# TI_ADC_VOLTAGE.net
KiCad netlist of a schematic drawn in Altium Designer
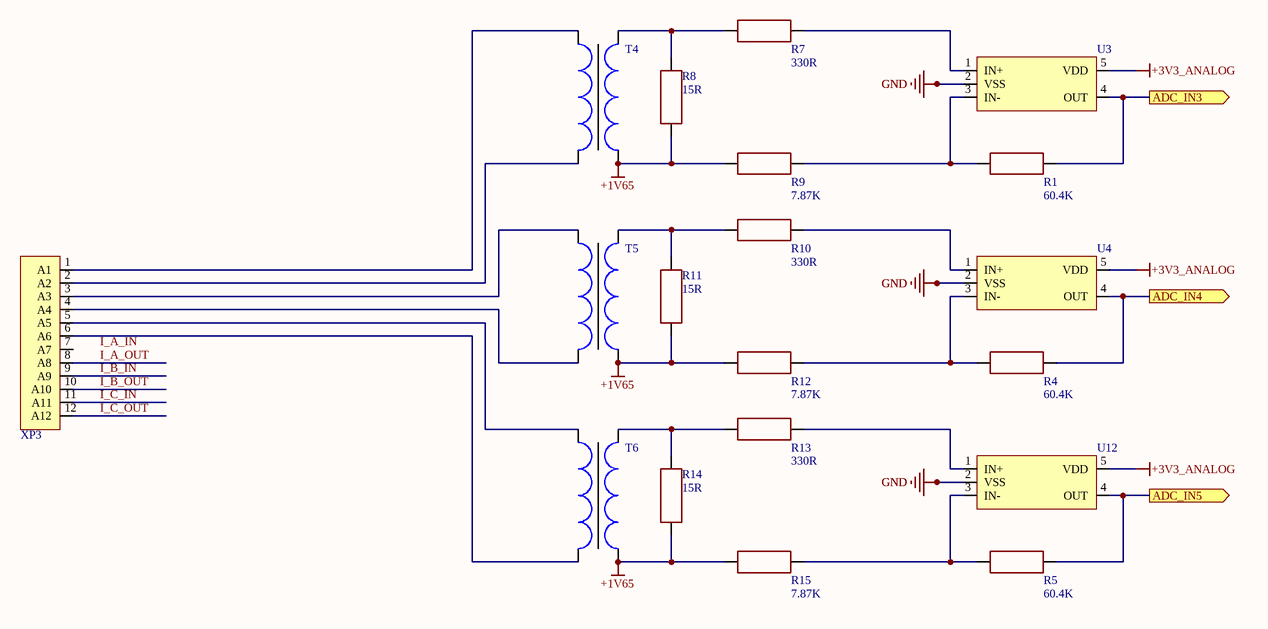
[diagram p0: TI_ADC_VOLTAGE.SchDoc]

(export (version "E")
  (design (tool "Eeschema 10.0.6"))
  (components
    (comp (ref "R1")
      (value "60.4K")
      (footprint "RES: 0603")
      (fields
        (field (name "POWER") "0.1W")
        (field (name "TOLERANCE") "±5%")
        (field (name "Comment") "Resistor_0603")
      )
      (libsource (lib "") (part "Resistor_0603_1"))
    )
    (comp (ref "R4")
      (value "60.4K")
      (footprint "RES: 0603")
      (fields
        (field (name "POWER") "0.1W")
        (field (name "TOLERANCE") "±5%")
        (field (name "Comment") "Resistor_0603")
      )
      (libsource (lib "") (part "Resistor_0603_1"))
    )
    (comp (ref "R5")
      (value "60.4K")
      (footprint "RES: 0603")
      (fields
        (field (name "POWER") "0.1W")
        (field (name "TOLERANCE") "±5%")
        (field (name "Comment") "Resistor_0603")
      )
      (libsource (lib "") (part "Resistor_0603_1"))
    )
    (comp (ref "R7")
      (value "330R")
      (footprint "RES: 0603")
      (fields
        (field (name "POWER") "0.1W")
        (field (name "TOLERANCE") "±5%")
        (field (name "Comment") "Resistor_0603")
      )
      (libsource (lib "resistor") (part "Resistor_0603"))
    )
    (comp (ref "R8")
      (value "15R")
      (footprint "RES: 0603")
      (fields
        (field (name "POWER") "0.1W")
        (field (name "TOLERANCE") "±5%")
        (field (name "Comment") "Resistor_0603")
      )
      (libsource (lib "") (part "Resistor_0603_1"))
    )
    (comp (ref "R9")
      (value "7.87K")
      (footprint "RES: 0603")
      (fields
        (field (name "POWER") "0.1W")
        (field (name "TOLERANCE") "±5%")
        (field (name "Comment") "Resistor_0603")
      )
      (libsource (lib "resistor") (part "Resistor_0603"))
    )
    (comp (ref "R10")
      (value "330R")
      (footprint "RES: 0603")
      (fields
        (field (name "POWER") "0.1W")
        (field (name "TOLERANCE") "±5%")
        (field (name "Comment") "Resistor_0603")
      )
      (libsource (lib "resistor") (part "Resistor_0603"))
    )
    (comp (ref "R11")
      (value "15R")
      (footprint "RES: 0603")
      (fields
        (field (name "POWER") "0.1W")
        (field (name "TOLERANCE") "±5%")
        (field (name "Comment") "Resistor_0603")
      )
      (libsource (lib "") (part "Resistor_0603_1"))
    )
    (comp (ref "R12")
      (value "7.87K")
      (footprint "RES: 0603")
      (fields
        (field (name "POWER") "0.1W")
        (field (name "TOLERANCE") "±5%")
        (field (name "Comment") "Resistor_0603")
      )
      (libsource (lib "resistor") (part "Resistor_0603"))
    )
    (comp (ref "R13")
      (value "330R")
      (footprint "RES: 0603")
      (fields
        (field (name "POWER") "0.1W")
        (field (name "TOLERANCE") "±5%")
        (field (name "Comment") "Resistor_0603")
      )
      (libsource (lib "resistor") (part "Resistor_0603"))
    )
    (comp (ref "R14")
      (value "15R")
      (footprint "RES: 0603")
      (fields
        (field (name "POWER") "0.1W")
        (field (name "TOLERANCE") "±5%")
        (field (name "Comment") "Resistor_0603")
      )
      (libsource (lib "") (part "Resistor_0603_1"))
    )
    (comp (ref "R15")
      (value "7.87K")
      (footprint "RES: 0603")
      (fields
        (field (name "POWER") "0.1W")
        (field (name "TOLERANCE") "±5%")
        (field (name "Comment") "Resistor_0603")
      )
      (libsource (lib "resistor") (part "Resistor_0603"))
    )
    (comp (ref "T4")
      (value "TV31B02")
      (footprint "TV31B02")
      (description "Current-type Voltage Transformer")
      (fields (field (name "MANUFACTURER") "YUANXING"))
      (libsource (lib "MY_INT_LIB") (part "TV31B02"))
    )
    (comp (ref "T5")
      (value "TV31B02")
      (footprint "TV31B02")
      (description "Current-type Voltage Transformer")
      (fields (field (name "MANUFACTURER") "YUANXING"))
      (libsource (lib "MY_INT_LIB") (part "TV31B02"))
    )
    (comp (ref "T6")
      (value "TV31B02")
      (footprint "TV31B02")
      (description "Current-type Voltage Transformer")
      (fields (field (name "MANUFACTURER") "YUANXING"))
      (libsource (lib "MY_INT_LIB") (part "TV31B02"))
    )
    (comp (ref "U3")
      (value "MCP6001U")
      (footprint "SOT-23-5")
      (description "1 MHz, Low-Power Op Amp")
      (fields (field (name "MANUFACTURER") "Microchip"))
      (libsource (lib "MY_INT_LIB") (part "MCP6001U"))
    )
    (comp (ref "U4")
      (value "MCP6001U")
      (footprint "SOT-23-5")
      (description "1 MHz, Low-Power Op Amp")
      (fields (field (name "MANUFACTURER") "Microchip"))
      (libsource (lib "MY_INT_LIB") (part "MCP6001U"))
    )
    (comp (ref "U12")
      (value "MCP6001U")
      (footprint "SOT-23-5")
      (description "1 MHz, Low-Power Op Amp")
      (fields (field (name "MANUFACTURER") "Microchip"))
      (libsource (lib "MY_INT_LIB") (part "MCP6001U"))
    )
    (comp (ref "XP3")
      (value "PLS-6 (DS1MSTB 2,5/12-GF-5,08021-1x6)")
      (footprint "MSTB 2,5/12-GF-5,08")
      (description "Surface Mount, Single row, 12 Positions, 5.08mm")
      (fields (field (name "MANUFACTURER") "Phoenix contact"))
      (libsource (lib "MY_INT_LIB") (part "MSTB 2,5/12-GF-5,08"))
    )
  )
  (nets
    (net (code "1") (name "+1V65") (class "Default")
      (node (ref "R11") (pin "2") (pinfunction "2_2") (pintype "passive"))
      (node (ref "R12") (pin "1") (pinfunction "1_1") (pintype "passive"))
      (node (ref "R14") (pin "2") (pinfunction "2_2") (pintype "passive"))
      (node (ref "R15") (pin "1") (pinfunction "1_1") (pintype "passive"))
      (node (ref "R8") (pin "2") (pinfunction "2_2") (pintype "passive"))
      (node (ref "R9") (pin "1") (pinfunction "1_1") (pintype "passive"))
      (node (ref "T4") (pin "2") (pinfunction "2_2") (pintype "passive"))
      (node (ref "T5") (pin "2") (pinfunction "2_2") (pintype "passive"))
      (node (ref "T6") (pin "2") (pinfunction "2_2") (pintype "passive"))
    )
    (net (code "2") (name "+3V3_ANALOG") (class "Default")
      (node (ref "U12") (pin "5") (pinfunction "VDD_5") (pintype "power_in"))
      (node (ref "U3") (pin "5") (pinfunction "VDD_5") (pintype "power_in"))
      (node (ref "U4") (pin "5") (pinfunction "VDD_5") (pintype "power_in"))
    )
    (net (code "3") (name "/ADC_IN3") (class "Default")
      (node (ref "R1") (pin "1") (pinfunction "1_1") (pintype "passive"))
      (node (ref "U3") (pin "4") (pinfunction "OUT_4") (pintype "passive"))
    )
    (net (code "4") (name "/ADC_IN4") (class "Default")
      (node (ref "R4") (pin "1") (pinfunction "1_1") (pintype "passive"))
      (node (ref "U4") (pin "4") (pinfunction "OUT_4") (pintype "passive"))
    )
    (net (code "5") (name "/ADC_IN5") (class "Default")
      (node (ref "R5") (pin "1") (pinfunction "1_1") (pintype "passive"))
      (node (ref "U12") (pin "4") (pinfunction "OUT_4") (pintype "passive"))
    )
    (net (code "7") (name "/I_A_OUT") (class "Default")
      (node (ref "XP3") (pin "8") (pinfunction "A8_8") (pintype "passive"))
    )
    (net (code "8") (name "/I_B_IN") (class "Default")
      (node (ref "XP3") (pin "9") (pinfunction "A9_9") (pintype "passive"))
    )
    (net (code "9") (name "/I_B_OUT") (class "Default")
      (node (ref "XP3") (pin "10") (pinfunction "A10_10") (pintype "passive"))
    )
    (net (code "10") (name "/I_C_IN") (class "Default")
      (node (ref "XP3") (pin "11") (pinfunction "A11_11") (pintype "passive"))
    )
    (net (code "11") (name "/I_C_OUT") (class "Default")
      (node (ref "XP3") (pin "12") (pinfunction "A12_12") (pintype "passive"))
    )
    (net (code "12") (name "GND") (class "Default")
      (node (ref "U12") (pin "2") (pinfunction "VSS_2") (pintype "power_in"))
      (node (ref "U3") (pin "2") (pinfunction "VSS_2") (pintype "power_in"))
      (node (ref "U4") (pin "2") (pinfunction "VSS_2") (pintype "power_in"))
    )
    (net (code "13") (name "Net-(R7-Pad1)") (class "Default")
      (node (ref "R7") (pin "1") (pinfunction "1_1") (pintype "passive"))
      (node (ref "R8") (pin "1") (pinfunction "1_1") (pintype "passive"))
      (node (ref "T4") (pin "1") (pinfunction "1_1") (pintype "passive"))
    )
    (net (code "14") (name "Net-(R10-Pad1)") (class "Default")
      (node (ref "R10") (pin "1") (pinfunction "1_1") (pintype "passive"))
      (node (ref "R11") (pin "1") (pinfunction "1_1") (pintype "passive"))
      (node (ref "T5") (pin "1") (pinfunction "1_1") (pintype "passive"))
    )
    (net (code "15") (name "Net-(R13-Pad1)") (class "Default")
      (node (ref "R13") (pin "1") (pinfunction "1_1") (pintype "passive"))
      (node (ref "R14") (pin "1") (pinfunction "1_1") (pintype "passive"))
      (node (ref "T6") (pin "1") (pinfunction "1_1") (pintype "passive"))
    )
    (net (code "16") (name "Net-(U3-IN+)") (class "Default")
      (node (ref "R7") (pin "2") (pinfunction "2_2") (pintype "passive"))
      (node (ref "U3") (pin "1") (pinfunction "IN+_1") (pintype "passive"))
    )
    (net (code "17") (name "Net-(U3-IN-)") (class "Default")
      (node (ref "R1") (pin "2") (pinfunction "2_2") (pintype "passive"))
      (node (ref "R9") (pin "2") (pinfunction "2_2") (pintype "passive"))
      (node (ref "U3") (pin "3") (pinfunction "IN-_3") (pintype "passive"))
    )
    (net (code "18") (name "Net-(U4-IN+)") (class "Default")
      (node (ref "R10") (pin "2") (pinfunction "2_2") (pintype "passive"))
      (node (ref "U4") (pin "1") (pinfunction "IN+_1") (pintype "passive"))
    )
    (net (code "19") (name "Net-(U4-IN-)") (class "Default")
      (node (ref "R12") (pin "2") (pinfunction "2_2") (pintype "passive"))
      (node (ref "R4") (pin "2") (pinfunction "2_2") (pintype "passive"))
      (node (ref "U4") (pin "3") (pinfunction "IN-_3") (pintype "passive"))
    )
    (net (code "20") (name "Net-(U12-IN+)") (class "Default")
      (node (ref "R13") (pin "2") (pinfunction "2_2") (pintype "passive"))
      (node (ref "U12") (pin "1") (pinfunction "IN+_1") (pintype "passive"))
    )
    (net (code "21") (name "Net-(U12-IN-)") (class "Default")
      (node (ref "R15") (pin "2") (pinfunction "2_2") (pintype "passive"))
      (node (ref "R5") (pin "2") (pinfunction "2_2") (pintype "passive"))
      (node (ref "U12") (pin "3") (pinfunction "IN-_3") (pintype "passive"))
    )
    (net (code "22") (name "Net-(XP3-A1)") (class "Default")
      (node (ref "T4") (pin "4") (pinfunction "4_4") (pintype "passive"))
      (node (ref "XP3") (pin "1") (pinfunction "A1_1") (pintype "passive"))
    )
    (net (code "23") (name "Net-(XP3-A2)") (class "Default")
      (node (ref "T4") (pin "3") (pinfunction "3_3") (pintype "passive"))
      (node (ref "XP3") (pin "2") (pinfunction "A2_2") (pintype "passive"))
    )
    (net (code "24") (name "Net-(XP3-A3)") (class "Default")
      (node (ref "T5") (pin "4") (pinfunction "4_4") (pintype "passive"))
      (node (ref "XP3") (pin "3") (pinfunction "A3_3") (pintype "passive"))
    )
    (net (code "25") (name "Net-(XP3-A4)") (class "Default")
      (node (ref "T5") (pin "3") (pinfunction "3_3") (pintype "passive"))
      (node (ref "XP3") (pin "4") (pinfunction "A4_4") (pintype "passive"))
    )
    (net (code "26") (name "Net-(XP3-A5)") (class "Default")
      (node (ref "T6") (pin "4") (pinfunction "4_4") (pintype "passive"))
      (node (ref "XP3") (pin "5") (pinfunction "A5_5") (pintype "passive"))
    )
    (net (code "27") (name "Net-(XP3-A6)") (class "Default")
      (node (ref "T6") (pin "3") (pinfunction "3_3") (pintype "passive"))
      (node (ref "XP3") (pin "6") (pinfunction "A6_6") (pintype "passive"))
    )
    (net (code "28") (name "unconnected-(XP3-A7-Pad7)") (class "Default")
      (node (ref "XP3") (pin "7") (pinfunction "A7_7") (pintype "passive"))
    )
  )
)
